# 5V_Load_Switches.net
KiCad netlist of a schematic drawn in Altium Designer
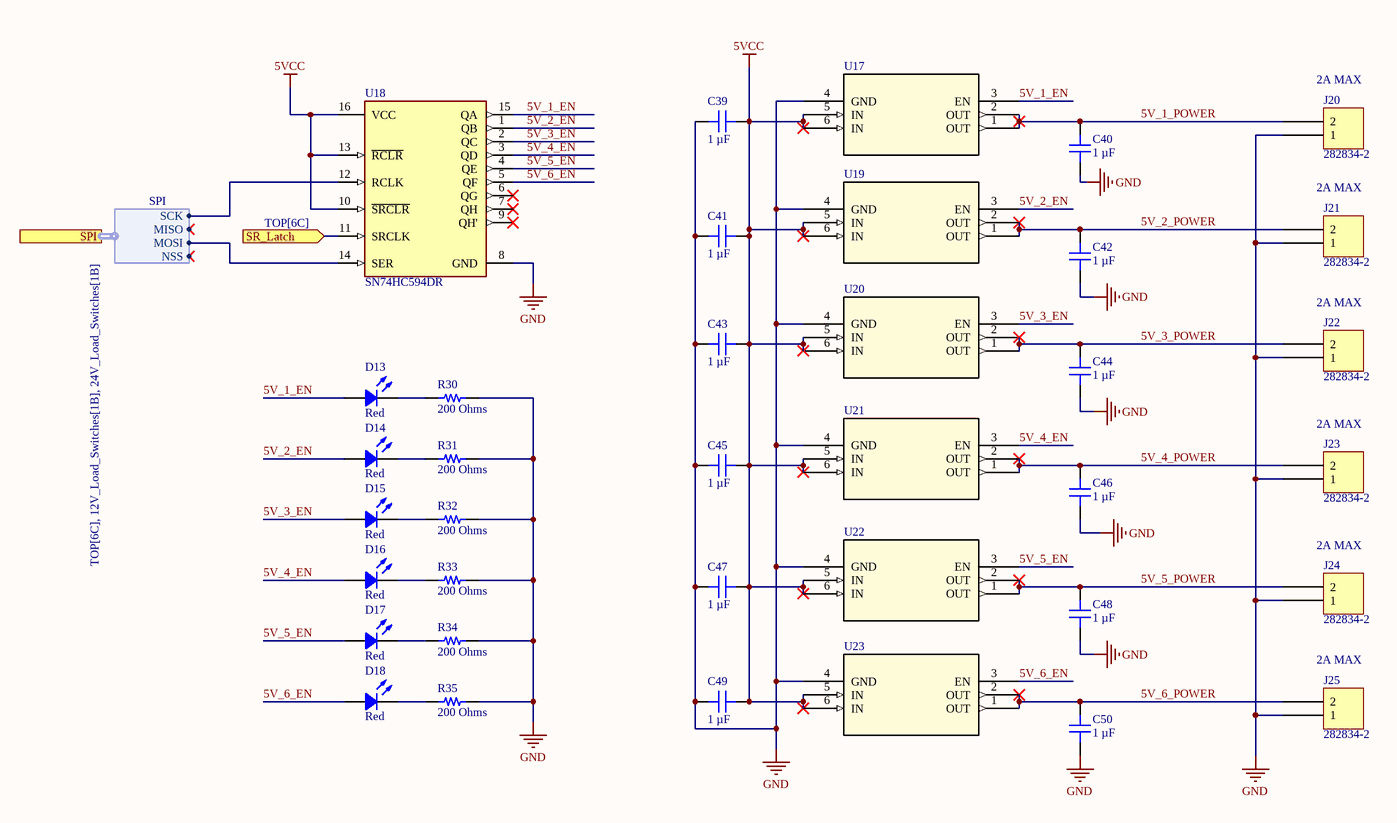
[diagram p0: 5V_Load_Switches.SchDoc]

(export (version "E")
  (design (tool "Eeschema 10.0.6"))
  (components
    (comp (ref "C39")
      (value "1 µF")
      (footprint "CAP 0805_2012")
      (description "CAP CER 1UF 50V X7R 0805")
      (fields
        (field (name "PART NUMBER") "0805B105K500CT")
        (field (name "MANUFACTURER") "Walsin Technology Corporation")
      )
      (libsource (lib "altium_library") (part "Capacitor"))
    )
    (comp (ref "C40")
      (value "1 µF")
      (footprint "CAP 0805_2012")
      (description "CAP CER 1UF 50V X7R 0805")
      (fields
        (field (name "PART NUMBER") "0805B105K500CT")
        (field (name "MANUFACTURER") "Walsin Technology Corporation")
      )
      (libsource (lib "altium_library") (part "Capacitor"))
    )
    (comp (ref "C41")
      (value "1 µF")
      (footprint "CAP 0805_2012")
      (description "CAP CER 1UF 50V X7R 0805")
      (fields
        (field (name "PART NUMBER") "0805B105K500CT")
        (field (name "MANUFACTURER") "Walsin Technology Corporation")
      )
      (libsource (lib "altium_library") (part "Capacitor"))
    )
    (comp (ref "C42")
      (value "1 µF")
      (footprint "CAP 0805_2012")
      (description "CAP CER 1UF 50V X7R 0805")
      (fields
        (field (name "PART NUMBER") "0805B105K500CT")
        (field (name "MANUFACTURER") "Walsin Technology Corporation")
      )
      (libsource (lib "altium_library") (part "Capacitor"))
    )
    (comp (ref "C43")
      (value "1 µF")
      (footprint "CAP 0805_2012")
      (description "CAP CER 1UF 50V X7R 0805")
      (fields
        (field (name "PART NUMBER") "0805B105K500CT")
        (field (name "MANUFACTURER") "Walsin Technology Corporation")
      )
      (libsource (lib "altium_library") (part "Capacitor"))
    )
    (comp (ref "C44")
      (value "1 µF")
      (footprint "CAP 0805_2012")
      (description "CAP CER 1UF 50V X7R 0805")
      (fields
        (field (name "PART NUMBER") "0805B105K500CT")
        (field (name "MANUFACTURER") "Walsin Technology Corporation")
      )
      (libsource (lib "altium_library") (part "Capacitor"))
    )
    (comp (ref "C45")
      (value "1 µF")
      (footprint "CAP 0805_2012")
      (description "CAP CER 1UF 50V X7R 0805")
      (fields
        (field (name "PART NUMBER") "0805B105K500CT")
        (field (name "MANUFACTURER") "Walsin Technology Corporation")
      )
      (libsource (lib "altium_library") (part "Capacitor"))
    )
    (comp (ref "C46")
      (value "1 µF")
      (footprint "CAP 0805_2012")
      (description "CAP CER 1UF 50V X7R 0805")
      (fields
        (field (name "PART NUMBER") "0805B105K500CT")
        (field (name "MANUFACTURER") "Walsin Technology Corporation")
      )
      (libsource (lib "altium_library") (part "Capacitor"))
    )
    (comp (ref "C47")
      (value "1 µF")
      (footprint "CAP 0805_2012")
      (description "CAP CER 1UF 50V X7R 0805")
      (fields
        (field (name "PART NUMBER") "0805B105K500CT")
        (field (name "MANUFACTURER") "Walsin Technology Corporation")
      )
      (libsource (lib "altium_library") (part "Capacitor"))
    )
    (comp (ref "C48")
      (value "1 µF")
      (footprint "CAP 0805_2012")
      (description "CAP CER 1UF 50V X7R 0805")
      (fields
        (field (name "PART NUMBER") "0805B105K500CT")
        (field (name "MANUFACTURER") "Walsin Technology Corporation")
      )
      (libsource (lib "altium_library") (part "Capacitor"))
    )
    (comp (ref "C49")
      (value "1 µF")
      (footprint "CAP 0805_2012")
      (description "0805 X7S 1UF10% 100V")
      (fields (field (name "PART NUMBER") "08051Z105KAT2A") (field (name "MANUFACTURER") "KYOCERA AVX"))
      (libsource (lib "Celestial Altium Library - altium_library") (part "Capacitor"))
    )
    (comp (ref "C50")
      (value "1 µF")
      (footprint "CAP 0805_2012")
      (description "CAP CER 1UF 50V X7R 0805")
      (fields
        (field (name "PART NUMBER") "0805B105K500CT")
        (field (name "MANUFACTURER") "Walsin Technology Corporation")
      )
      (libsource (lib "altium_library") (part "Capacitor"))
    )
    (comp (ref "D13")
      (value "Red")
      (footprint "LED 0603_1608 RED")
      (description "LED RED CLEAR 2SMD")
      (fields
        (field (name "PART NUMBER") "19-213SDRC/S259/TR8")
        (field (name "MANUFACTURER") "Everlight Electronics Co Ltd")
      )
      (libsource (lib "Celestial Altium Library - altium_library") (part "LED"))
    )
    (comp (ref "D14")
      (value "Red")
      (footprint "LED 0603_1608 RED")
      (description "LED RED CLEAR 2SMD")
      (fields
        (field (name "PART NUMBER") "19-213SDRC/S259/TR8")
        (field (name "MANUFACTURER") "Everlight Electronics Co Ltd")
      )
      (libsource (lib "Celestial Altium Library - altium_library") (part "LED"))
    )
    (comp (ref "D15")
      (value "Red")
      (footprint "LED 0603_1608 RED")
      (description "LED RED CLEAR 2SMD")
      (fields
        (field (name "PART NUMBER") "19-213SDRC/S259/TR8")
        (field (name "MANUFACTURER") "Everlight Electronics Co Ltd")
      )
      (libsource (lib "Celestial Altium Library - altium_library") (part "LED"))
    )
    (comp (ref "D16")
      (value "Red")
      (footprint "LED 0603_1608 RED")
      (description "LED RED CLEAR 2SMD")
      (fields
        (field (name "PART NUMBER") "19-213SDRC/S259/TR8")
        (field (name "MANUFACTURER") "Everlight Electronics Co Ltd")
      )
      (libsource (lib "Celestial Altium Library - altium_library") (part "LED"))
    )
    (comp (ref "D17")
      (value "Red")
      (footprint "LED 0603_1608 RED")
      (description "LED RED CLEAR 2SMD")
      (fields
        (field (name "PART NUMBER") "19-213SDRC/S259/TR8")
        (field (name "MANUFACTURER") "Everlight Electronics Co Ltd")
      )
      (libsource (lib "Celestial Altium Library - altium_library") (part "LED"))
    )
    (comp (ref "D18")
      (value "Red")
      (footprint "LED 0603_1608 RED")
      (description "LED RED CLEAR 2SMD")
      (fields
        (field (name "PART NUMBER") "19-213SDRC/S259/TR8")
        (field (name "MANUFACTURER") "Everlight Electronics Co Ltd")
      )
      (libsource (lib "Celestial Altium Library - altium_library") (part "LED"))
    )
    (comp (ref "J20")
      (value "282834-2")
      (footprint "TE 282834-2")
      (description "TERM BLK 2P SIDE ENT 2.54MM PCB")
      (fields (field (name "MANUFACTURER") "TE Connectivity AMP Connectors") (field (name "VOLTAGE") "150V"))
      (libsource (lib "altium_library") (part "2 Pin"))
    )
    (comp (ref "J21")
      (value "282834-2")
      (footprint "TE 282834-2")
      (description "TERM BLK 2P SIDE ENT 2.54MM PCB")
      (fields (field (name "MANUFACTURER") "TE Connectivity AMP Connectors") (field (name "VOLTAGE") "150V"))
      (libsource (lib "altium_library") (part "2 Pin"))
    )
    (comp (ref "J22")
      (value "282834-2")
      (footprint "TE 282834-2")
      (description "TERM BLK 2P SIDE ENT 2.54MM PCB")
      (fields (field (name "MANUFACTURER") "TE Connectivity AMP Connectors") (field (name "VOLTAGE") "150V"))
      (libsource (lib "altium_library") (part "2 Pin"))
    )
    (comp (ref "J23")
      (value "282834-2")
      (footprint "TE 282834-2")
      (description "TERM BLK 2P SIDE ENT 2.54MM PCB")
      (fields (field (name "MANUFACTURER") "TE Connectivity AMP Connectors") (field (name "VOLTAGE") "150V"))
      (libsource (lib "altium_library") (part "2 Pin"))
    )
    (comp (ref "J24")
      (value "282834-2")
      (footprint "TE 282834-2")
      (description "TERM BLK 2P SIDE ENT 2.54MM PCB")
      (fields (field (name "MANUFACTURER") "TE Connectivity AMP Connectors") (field (name "VOLTAGE") "150V"))
      (libsource (lib "altium_library") (part "2 Pin"))
    )
    (comp (ref "J25")
      (value "282834-2")
      (footprint "TE 282834-2")
      (description "TERM BLK 2P SIDE ENT 2.54MM PCB")
      (fields (field (name "MANUFACTURER") "TE Connectivity AMP Connectors") (field (name "VOLTAGE") "150V"))
      (libsource (lib "altium_library") (part "2 Pin"))
    )
    (comp (ref "R30")
      (value "200 Ohms")
      (footprint "RES 0603_1608")
      (description "RES 200 OHM 0.1% 1/5W 0603")
      (fields
        (field (name "PART NUMBER") "RS73F1JTTD2000B")
        (field (name "MANUFACTURER") "KOA Speer Electronics, Inc.")
      )
      (libsource (lib "Celestial Altium Library - altium_library") (part "Resistor"))
    )
    (comp (ref "R31")
      (value "200 Ohms")
      (footprint "RES 0603_1608")
      (description "RES 200 OHM 0.1% 1/5W 0603")
      (fields
        (field (name "PART NUMBER") "RS73F1JTTD2000B")
        (field (name "MANUFACTURER") "KOA Speer Electronics, Inc.")
      )
      (libsource (lib "Celestial Altium Library - altium_library") (part "Resistor"))
    )
    (comp (ref "R32")
      (value "200 Ohms")
      (footprint "RES 0603_1608")
      (description "RES 200 OHM 0.1% 1/5W 0603")
      (fields
        (field (name "PART NUMBER") "RS73F1JTTD2000B")
        (field (name "MANUFACTURER") "KOA Speer Electronics, Inc.")
      )
      (libsource (lib "Celestial Altium Library - altium_library") (part "Resistor"))
    )
    (comp (ref "R33")
      (value "200 Ohms")
      (footprint "RES 0603_1608")
      (description "RES 200 OHM 0.1% 1/5W 0603")
      (fields
        (field (name "PART NUMBER") "RS73F1JTTD2000B")
        (field (name "MANUFACTURER") "KOA Speer Electronics, Inc.")
      )
      (libsource (lib "Celestial Altium Library - altium_library") (part "Resistor"))
    )
    (comp (ref "R34")
      (value "200 Ohms")
      (footprint "RES 0603_1608")
      (description "RES 200 OHM 0.1% 1/5W 0603")
      (fields
        (field (name "PART NUMBER") "RS73F1JTTD2000B")
        (field (name "MANUFACTURER") "KOA Speer Electronics, Inc.")
      )
      (libsource (lib "Celestial Altium Library - altium_library") (part "Resistor"))
    )
    (comp (ref "R35")
      (value "200 Ohms")
      (footprint "RES 0603_1608")
      (description "RES 200 OHM 0.1% 1/5W 0603")
      (fields
        (field (name "PART NUMBER") "RS73F1JTTD2000B")
        (field (name "MANUFACTURER") "KOA Speer Electronics, Inc.")
      )
      (libsource (lib "Celestial Altium Library - altium_library") (part "Resistor"))
    )
    (comp (ref "U17")
      (value "~")
      (footprint "SIP32510DT-T1-GE3_VIS")
      (description "No Description Available")
      (fields
        (field (name "MANUFACTURER_PART_NUMBER") "SIP32510DT-T1-GE3")
        (field (name "COPYRIGHT") "Copyright (C) 2023 Ultra Librarian. All rights reserved.")
      )
      (libsource (lib "SIP32510DT-T1-GE3") (part "SIP32510DT-T1-GE3"))
    )
    (comp (ref "U18")
      (value "SN74HC594DR")
      (footprint "FP-D0016A-IPC_A")
      (description "IC SHIFT REGISTER 8BIT 16-SOIC")
      (libsource (lib "Altium Content Vault") (part "6ffdf0eb1487316571b39b71ede2db7"))
    )
    (comp (ref "U19")
      (value "~")
      (footprint "SIP32510DT-T1-GE3_VIS")
      (description "No Description Available")
      (fields
        (field (name "MANUFACTURER_PART_NUMBER") "SIP32510DT-T1-GE3")
        (field (name "COPYRIGHT") "Copyright (C) 2023 Ultra Librarian. All rights reserved.")
      )
      (libsource (lib "SIP32510DT-T1-GE3") (part "SIP32510DT-T1-GE3"))
    )
    (comp (ref "U20")
      (value "~")
      (footprint "SIP32510DT-T1-GE3_VIS")
      (description "No Description Available")
      (fields
        (field (name "MANUFACTURER_PART_NUMBER") "SIP32510DT-T1-GE3")
        (field (name "COPYRIGHT") "Copyright (C) 2023 Ultra Librarian. All rights reserved.")
      )
      (libsource (lib "SIP32510DT-T1-GE3") (part "SIP32510DT-T1-GE3"))
    )
    (comp (ref "U21")
      (value "~")
      (footprint "SIP32510DT-T1-GE3_VIS")
      (description "No Description Available")
      (fields
        (field (name "MANUFACTURER_PART_NUMBER") "SIP32510DT-T1-GE3")
        (field (name "COPYRIGHT") "Copyright (C) 2023 Ultra Librarian. All rights reserved.")
      )
      (libsource (lib "SIP32510DT-T1-GE3") (part "SIP32510DT-T1-GE3"))
    )
    (comp (ref "U22")
      (value "~")
      (footprint "SIP32510DT-T1-GE3_VIS")
      (description "No Description Available")
      (fields
        (field (name "MANUFACTURER_PART_NUMBER") "SIP32510DT-T1-GE3")
        (field (name "COPYRIGHT") "Copyright (C) 2023 Ultra Librarian. All rights reserved.")
      )
      (libsource (lib "SIP32510DT-T1-GE3") (part "SIP32510DT-T1-GE3"))
    )
    (comp (ref "U23")
      (value "~")
      (footprint "SIP32510DT-T1-GE3_VIS")
      (description "No Description Available")
      (fields
        (field (name "MANUFACTURER_PART_NUMBER") "SIP32510DT-T1-GE3")
        (field (name "COPYRIGHT") "Copyright (C) 2023 Ultra Librarian. All rights reserved.")
      )
      (libsource (lib "SIP32510DT-T1-GE3") (part "SIP32510DT-T1-GE3"))
    )
  )
  (nets
    (net (code "2") (name "/5V_1_EN") (class "Default")
      (node (ref "D13") (pin "1") (pinfunction "1_1") (pintype "passive"))
      (node (ref "U17") (pin "3") (pinfunction "EN_3") (pintype "passive"))
      (node (ref "U18") (pin "15") (pinfunction "QA_15") (pintype "output"))
    )
    (net (code "3") (name "/5V_1_POWER") (class "Default")
      (node (ref "C40") (pin "2") (pinfunction "2_2") (pintype "passive"))
      (node (ref "J20") (pin "2") (pinfunction "2_2") (pintype "passive"))
      (node (ref "U17") (pin "1") (pinfunction "OUT_1") (pintype "output"))
      (node (ref "U17") (pin "2") (pinfunction "OUT_2") (pintype "output"))
    )
    (net (code "4") (name "/5V_2_EN") (class "Default")
      (node (ref "D14") (pin "1") (pinfunction "1_1") (pintype "passive"))
      (node (ref "U18") (pin "1") (pinfunction "QB_1") (pintype "output"))
      (node (ref "U19") (pin "3") (pinfunction "EN_3") (pintype "passive"))
    )
    (net (code "5") (name "/5V_2_POWER") (class "Default")
      (node (ref "C42") (pin "2") (pinfunction "2_2") (pintype "passive"))
      (node (ref "J21") (pin "2") (pinfunction "2_2") (pintype "passive"))
      (node (ref "U19") (pin "1") (pinfunction "OUT_1") (pintype "output"))
      (node (ref "U19") (pin "2") (pinfunction "OUT_2") (pintype "output"))
    )
    (net (code "6") (name "/5V_3_EN") (class "Default")
      (node (ref "D15") (pin "1") (pinfunction "1_1") (pintype "passive"))
      (node (ref "U18") (pin "2") (pinfunction "QC_2") (pintype "output"))
      (node (ref "U20") (pin "3") (pinfunction "EN_3") (pintype "passive"))
    )
    (net (code "7") (name "/5V_3_POWER") (class "Default")
      (node (ref "C44") (pin "2") (pinfunction "2_2") (pintype "passive"))
      (node (ref "J22") (pin "2") (pinfunction "2_2") (pintype "passive"))
      (node (ref "U20") (pin "1") (pinfunction "OUT_1") (pintype "output"))
      (node (ref "U20") (pin "2") (pinfunction "OUT_2") (pintype "output"))
    )
    (net (code "8") (name "/5V_4_EN") (class "Default")
      (node (ref "D16") (pin "1") (pinfunction "1_1") (pintype "passive"))
      (node (ref "U18") (pin "3") (pinfunction "QD_3") (pintype "output"))
      (node (ref "U21") (pin "3") (pinfunction "EN_3") (pintype "passive"))
    )
    (net (code "9") (name "/5V_4_POWER") (class "Default")
      (node (ref "C46") (pin "2") (pinfunction "2_2") (pintype "passive"))
      (node (ref "J23") (pin "2") (pinfunction "2_2") (pintype "passive"))
      (node (ref "U21") (pin "1") (pinfunction "OUT_1") (pintype "output"))
      (node (ref "U21") (pin "2") (pinfunction "OUT_2") (pintype "output"))
    )
    (net (code "10") (name "/5V_5_EN") (class "Default")
      (node (ref "D17") (pin "1") (pinfunction "1_1") (pintype "passive"))
      (node (ref "U18") (pin "4") (pinfunction "QE_4") (pintype "output"))
      (node (ref "U22") (pin "3") (pinfunction "EN_3") (pintype "passive"))
    )
    (net (code "11") (name "/5V_5_POWER") (class "Default")
      (node (ref "C48") (pin "2") (pinfunction "2_2") (pintype "passive"))
      (node (ref "J24") (pin "2") (pinfunction "2_2") (pintype "passive"))
      (node (ref "U22") (pin "1") (pinfunction "OUT_1") (pintype "output"))
      (node (ref "U22") (pin "2") (pinfunction "OUT_2") (pintype "output"))
    )
    (net (code "12") (name "/5V_6_EN") (class "Default")
      (node (ref "D18") (pin "1") (pinfunction "1_1") (pintype "passive"))
      (node (ref "U18") (pin "5") (pinfunction "QF_5") (pintype "output"))
      (node (ref "U23") (pin "3") (pinfunction "EN_3") (pintype "passive"))
    )
    (net (code "13") (name "/5V_6_POWER") (class "Default")
      (node (ref "C50") (pin "2") (pinfunction "2_2") (pintype "passive"))
      (node (ref "J25") (pin "2") (pinfunction "2_2") (pintype "passive"))
      (node (ref "U23") (pin "1") (pinfunction "OUT_1") (pintype "output"))
      (node (ref "U23") (pin "2") (pinfunction "OUT_2") (pintype "output"))
    )
    (net (code "14") (name "/MOSI") (class "Default")
      (node (ref "U18") (pin "14") (pinfunction "SER_14") (pintype "input"))
    )
    (net (code "15") (name "/SCK") (class "Default")
      (node (ref "U18") (pin "12") (pinfunction "RCLK_12") (pintype "input"))
    )
    (net (code "16") (name "/SR_Latch") (class "Default")
      (node (ref "U18") (pin "11") (pinfunction "SRCLK_11") (pintype "input"))
    )
    (net (code "18") (name "5VCC") (class "Default")
      (node (ref "C39") (pin "2") (pinfunction "2_2") (pintype "passive"))
      (node (ref "C41") (pin "2") (pinfunction "2_2") (pintype "passive"))
      (node (ref "C43") (pin "2") (pinfunction "2_2") (pintype "passive"))
      (node (ref "C45") (pin "2") (pinfunction "2_2") (pintype "passive"))
      (node (ref "C47") (pin "2") (pinfunction "2_2") (pintype "passive"))
      (node (ref "C49") (pin "2") (pinfunction "2_2") (pintype "passive"))
      (node (ref "U17") (pin "5") (pinfunction "IN_5") (pintype "input"))
      (node (ref "U17") (pin "6") (pinfunction "IN_6") (pintype "input"))
      (node (ref "U18") (pin "10") (pinfunction "~{SRCLR}_10") (pintype "input"))
      (node (ref "U18") (pin "13") (pinfunction "~{RCLR}_13") (pintype "input"))
      (node (ref "U18") (pin "16") (pinfunction "VCC_16") (pintype "power_in"))
      (node (ref "U19") (pin "5") (pinfunction "IN_5") (pintype "input"))
      (node (ref "U19") (pin "6") (pinfunction "IN_6") (pintype "input"))
      (node (ref "U20") (pin "5") (pinfunction "IN_5") (pintype "input"))
      (node (ref "U20") (pin "6") (pinfunction "IN_6") (pintype "input"))
      (node (ref "U21") (pin "5") (pinfunction "IN_5") (pintype "input"))
      (node (ref "U21") (pin "6") (pinfunction "IN_6") (pintype "input"))
      (node (ref "U22") (pin "5") (pinfunction "IN_5") (pintype "input"))
      (node (ref "U22") (pin "6") (pinfunction "IN_6") (pintype "input"))
      (node (ref "U23") (pin "5") (pinfunction "IN_5") (pintype "input"))
      (node (ref "U23") (pin "6") (pinfunction "IN_6") (pintype "input"))
    )
    (net (code "19") (name "GND") (class "Default")
      (node (ref "C39") (pin "1") (pinfunction "1_1") (pintype "passive"))
      (node (ref "C40") (pin "1") (pinfunction "1_1") (pintype "passive"))
      (node (ref "C41") (pin "1") (pinfunction "1_1") (pintype "passive"))
      (node (ref "C42") (pin "1") (pinfunction "1_1") (pintype "passive"))
      (node (ref "C43") (pin "1") (pinfunction "1_1") (pintype "passive"))
      (node (ref "C44") (pin "1") (pinfunction "1_1") (pintype "passive"))
      (node (ref "C45") (pin "1") (pinfunction "1_1") (pintype "passive"))
      (node (ref "C46") (pin "1") (pinfunction "1_1") (pintype "passive"))
      (node (ref "C47") (pin "1") (pinfunction "1_1") (pintype "passive"))
      (node (ref "C48") (pin "1") (pinfunction "1_1") (pintype "passive"))
      (node (ref "C49") (pin "1") (pinfunction "1_1") (pintype "passive"))
      (node (ref "C50") (pin "1") (pinfunction "1_1") (pintype "passive"))
      (node (ref "J20") (pin "1") (pinfunction "1_1") (pintype "passive"))
      (node (ref "J21") (pin "1") (pinfunction "1_1") (pintype "passive"))
      (node (ref "J22") (pin "1") (pinfunction "1_1") (pintype "passive"))
      (node (ref "J23") (pin "1") (pinfunction "1_1") (pintype "passive"))
      (node (ref "J24") (pin "1") (pinfunction "1_1") (pintype "passive"))
      (node (ref "J25") (pin "1") (pinfunction "1_1") (pintype "passive"))
      (node (ref "R30") (pin "2") (pinfunction "2_2") (pintype "passive"))
      (node (ref "R31") (pin "2") (pinfunction "2_2") (pintype "passive"))
      (node (ref "R32") (pin "2") (pinfunction "2_2") (pintype "passive"))
      (node (ref "R33") (pin "2") (pinfunction "2_2") (pintype "passive"))
      (node (ref "R34") (pin "2") (pinfunction "2_2") (pintype "passive"))
      (node (ref "R35") (pin "2") (pinfunction "2_2") (pintype "passive"))
      (node (ref "U17") (pin "4") (pinfunction "GND_4") (pintype "power_in"))
      (node (ref "U18") (pin "8") (pinfunction "GND_8") (pintype "power_in"))
      (node (ref "U19") (pin "4") (pinfunction "GND_4") (pintype "power_in"))
      (node (ref "U20") (pin "4") (pinfunction "GND_4") (pintype "power_in"))
      (node (ref "U21") (pin "4") (pinfunction "GND_4") (pintype "power_in"))
      (node (ref "U22") (pin "4") (pinfunction "GND_4") (pintype "power_in"))
      (node (ref "U23") (pin "4") (pinfunction "GND_4") (pintype "power_in"))
    )
    (net (code "20") (name "Net-(D13-Pad2)") (class "Default")
      (node (ref "D13") (pin "2") (pinfunction "2_2") (pintype "passive"))
      (node (ref "R30") (pin "1") (pinfunction "1_1") (pintype "passive"))
    )
    (net (code "21") (name "Net-(D14-Pad2)") (class "Default")
      (node (ref "D14") (pin "2") (pinfunction "2_2") (pintype "passive"))
      (node (ref "R31") (pin "1") (pinfunction "1_1") (pintype "passive"))
    )
    (net (code "22") (name "Net-(D15-Pad2)") (class "Default")
      (node (ref "D15") (pin "2") (pinfunction "2_2") (pintype "passive"))
      (node (ref "R32") (pin "1") (pinfunction "1_1") (pintype "passive"))
    )
    (net (code "23") (name "Net-(D16-Pad2)") (class "Default")
      (node (ref "D16") (pin "2") (pinfunction "2_2") (pintype "passive"))
      (node (ref "R33") (pin "1") (pinfunction "1_1") (pintype "passive"))
    )
    (net (code "24") (name "Net-(D17-Pad2)") (class "Default")
      (node (ref "D17") (pin "2") (pinfunction "2_2") (pintype "passive"))
      (node (ref "R34") (pin "1") (pinfunction "1_1") (pintype "passive"))
    )
    (net (code "25") (name "Net-(D18-Pad2)") (class "Default")
      (node (ref "D18") (pin "2") (pinfunction "2_2") (pintype "passive"))
      (node (ref "R35") (pin "1") (pinfunction "1_1") (pintype "passive"))
    )
    (net (code "26") (name "unconnected-(U18-QG-Pad6)") (class "Default")
      (node (ref "U18") (pin "6") (pinfunction "QG_6") (pintype "output+no_connect"))
    )
    (net (code "27") (name "unconnected-(U18-QH'-Pad9)") (class "Default")
      (node (ref "U18") (pin "9") (pinfunction "QH'_9") (pintype "output+no_connect"))
    )
    (net (code "28") (name "unconnected-(U18-QH-Pad7)") (class "Default")
      (node (ref "U18") (pin "7") (pinfunction "QH_7") (pintype "output+no_connect"))
    )
  )
)
